# slot.net
KiCad netlist of a schematic drawn in Altium Designer
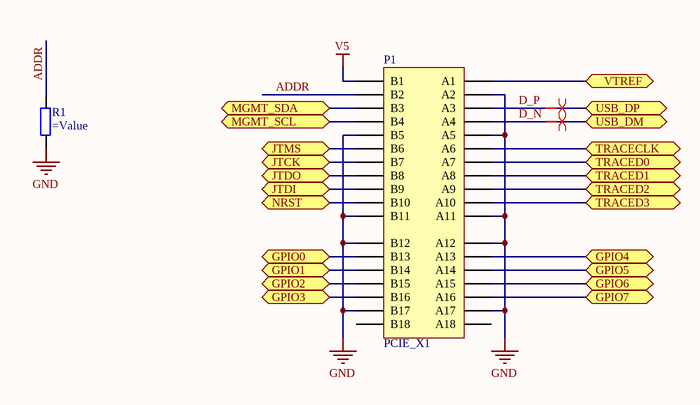
[diagram p0: slot.SchDoc]

(export (version "E")
  (design (tool "Eeschema 10.0.6"))
  (components
    (comp (ref "P1") (value "PCIE_X1") (footprint "PCIE_X1_SMT") (libsource (lib "misc") (part "PCIE_X1")))
    (comp (ref "R1") (value "~") (footprint "0402") (libsource (lib "misc") (part "Resistor")))
  )
  (nets
    (net (code "1") (name "/ADDR") (class "Default")
      (node (ref "P1") (pin "B2") (pinfunction "B2_B2") (pintype "passive"))
      (node (ref "R1") (pin "2") (pinfunction "2_2") (pintype "passive"))
    )
    (net (code "2") (name "/D_N") (class "Default")
      (node (ref "P1") (pin "A4") (pinfunction "A4_A4") (pintype "passive"))
    )
    (net (code "3") (name "/D_P") (class "Default")
      (node (ref "P1") (pin "A3") (pinfunction "A3_A3") (pintype "passive"))
    )
    (net (code "4") (name "/GPIO0") (class "Default")
      (node (ref "P1") (pin "B13") (pinfunction "B13_B13") (pintype "passive"))
    )
    (net (code "5") (name "/GPIO1") (class "Default")
      (node (ref "P1") (pin "B14") (pinfunction "B14_B14") (pintype "passive"))
    )
    (net (code "6") (name "/GPIO2") (class "Default")
      (node (ref "P1") (pin "B15") (pinfunction "B15_B15") (pintype "passive"))
    )
    (net (code "7") (name "/GPIO3") (class "Default")
      (node (ref "P1") (pin "B16") (pinfunction "B16_B16") (pintype "passive"))
    )
    (net (code "8") (name "/GPIO4") (class "Default")
      (node (ref "P1") (pin "A13") (pinfunction "A13_A13") (pintype "passive"))
    )
    (net (code "9") (name "/GPIO5") (class "Default")
      (node (ref "P1") (pin "A14") (pinfunction "A14_A14") (pintype "passive"))
    )
    (net (code "10") (name "/GPIO6") (class "Default")
      (node (ref "P1") (pin "A15") (pinfunction "A15_A15") (pintype "passive"))
    )
    (net (code "11") (name "/GPIO7") (class "Default")
      (node (ref "P1") (pin "A16") (pinfunction "A16_A16") (pintype "passive"))
    )
    (net (code "12") (name "/JTCK") (class "Default")
      (node (ref "P1") (pin "B7") (pinfunction "B7_B7") (pintype "passive"))
    )
    (net (code "13") (name "/JTDI") (class "Default")
      (node (ref "P1") (pin "B9") (pinfunction "B9_B9") (pintype "passive"))
    )
    (net (code "14") (name "/JTDO") (class "Default")
      (node (ref "P1") (pin "B8") (pinfunction "B8_B8") (pintype "passive"))
    )
    (net (code "15") (name "/JTMS") (class "Default")
      (node (ref "P1") (pin "B6") (pinfunction "B6_B6") (pintype "passive"))
    )
    (net (code "16") (name "/MGMT_SCL") (class "Default")
      (node (ref "P1") (pin "B4") (pinfunction "B4_B4") (pintype "passive"))
    )
    (net (code "17") (name "/MGMT_SDA") (class "Default")
      (node (ref "P1") (pin "B3") (pinfunction "B3_B3") (pintype "passive"))
    )
    (net (code "18") (name "/NRST") (class "Default")
      (node (ref "P1") (pin "B10") (pinfunction "B10_B10") (pintype "passive"))
    )
    (net (code "19") (name "/TRACECLK") (class "Default")
      (node (ref "P1") (pin "A6") (pinfunction "A6_A6") (pintype "passive"))
    )
    (net (code "20") (name "/TRACED0") (class "Default")
      (node (ref "P1") (pin "A7") (pinfunction "A7_A7") (pintype "passive"))
    )
    (net (code "21") (name "/TRACED1") (class "Default")
      (node (ref "P1") (pin "A8") (pinfunction "A8_A8") (pintype "passive"))
    )
    (net (code "22") (name "/TRACED2") (class "Default")
      (node (ref "P1") (pin "A9") (pinfunction "A9_A9") (pintype "passive"))
    )
    (net (code "23") (name "/TRACED3") (class "Default")
      (node (ref "P1") (pin "A10") (pinfunction "A10_A10") (pintype "passive"))
    )
    (net (code "24") (name "/VTREF") (class "Default")
      (node (ref "P1") (pin "A1") (pinfunction "A1_A1") (pintype "passive"))
    )
    (net (code "25") (name "GND") (class "Default")
      (node (ref "P1") (pin "A11") (pinfunction "A11_A11") (pintype "passive"))
      (node (ref "P1") (pin "A12") (pinfunction "A12_A12") (pintype "passive"))
      (node (ref "P1") (pin "A17") (pinfunction "A17_A17") (pintype "passive"))
      (node (ref "P1") (pin "A2") (pinfunction "A2_A2") (pintype "passive"))
      (node (ref "P1") (pin "A5") (pinfunction "A5_A5") (pintype "passive"))
      (node (ref "P1") (pin "B11") (pinfunction "B11_B11") (pintype "passive"))
      (node (ref "P1") (pin "B12") (pinfunction "B12_B12") (pintype "passive"))
      (node (ref "P1") (pin "B17") (pinfunction "B17_B17") (pintype "passive"))
      (node (ref "P1") (pin "B5") (pinfunction "B5_B5") (pintype "passive"))
      (node (ref "R1") (pin "1") (pinfunction "1_1") (pintype "passive"))
    )
    (net (code "26") (name "V5") (class "Default")
      (node (ref "P1") (pin "B1") (pinfunction "B1_B1") (pintype "passive"))
    )
    (net (code "27") (name "unconnected-(P1-PadA18)") (class "Default")
      (node (ref "P1") (pin "A18") (pinfunction "A18_A18") (pintype "passive"))
    )
    (net (code "28") (name "unconnected-(P1-PadB18)") (class "Default")
      (node (ref "P1") (pin "B18") (pinfunction "B18_B18") (pintype "passive"))
    )
  )
)
